# pmi_encoder_rs422_decoder.net
KiCad netlist of a schematic drawn in EAGLE
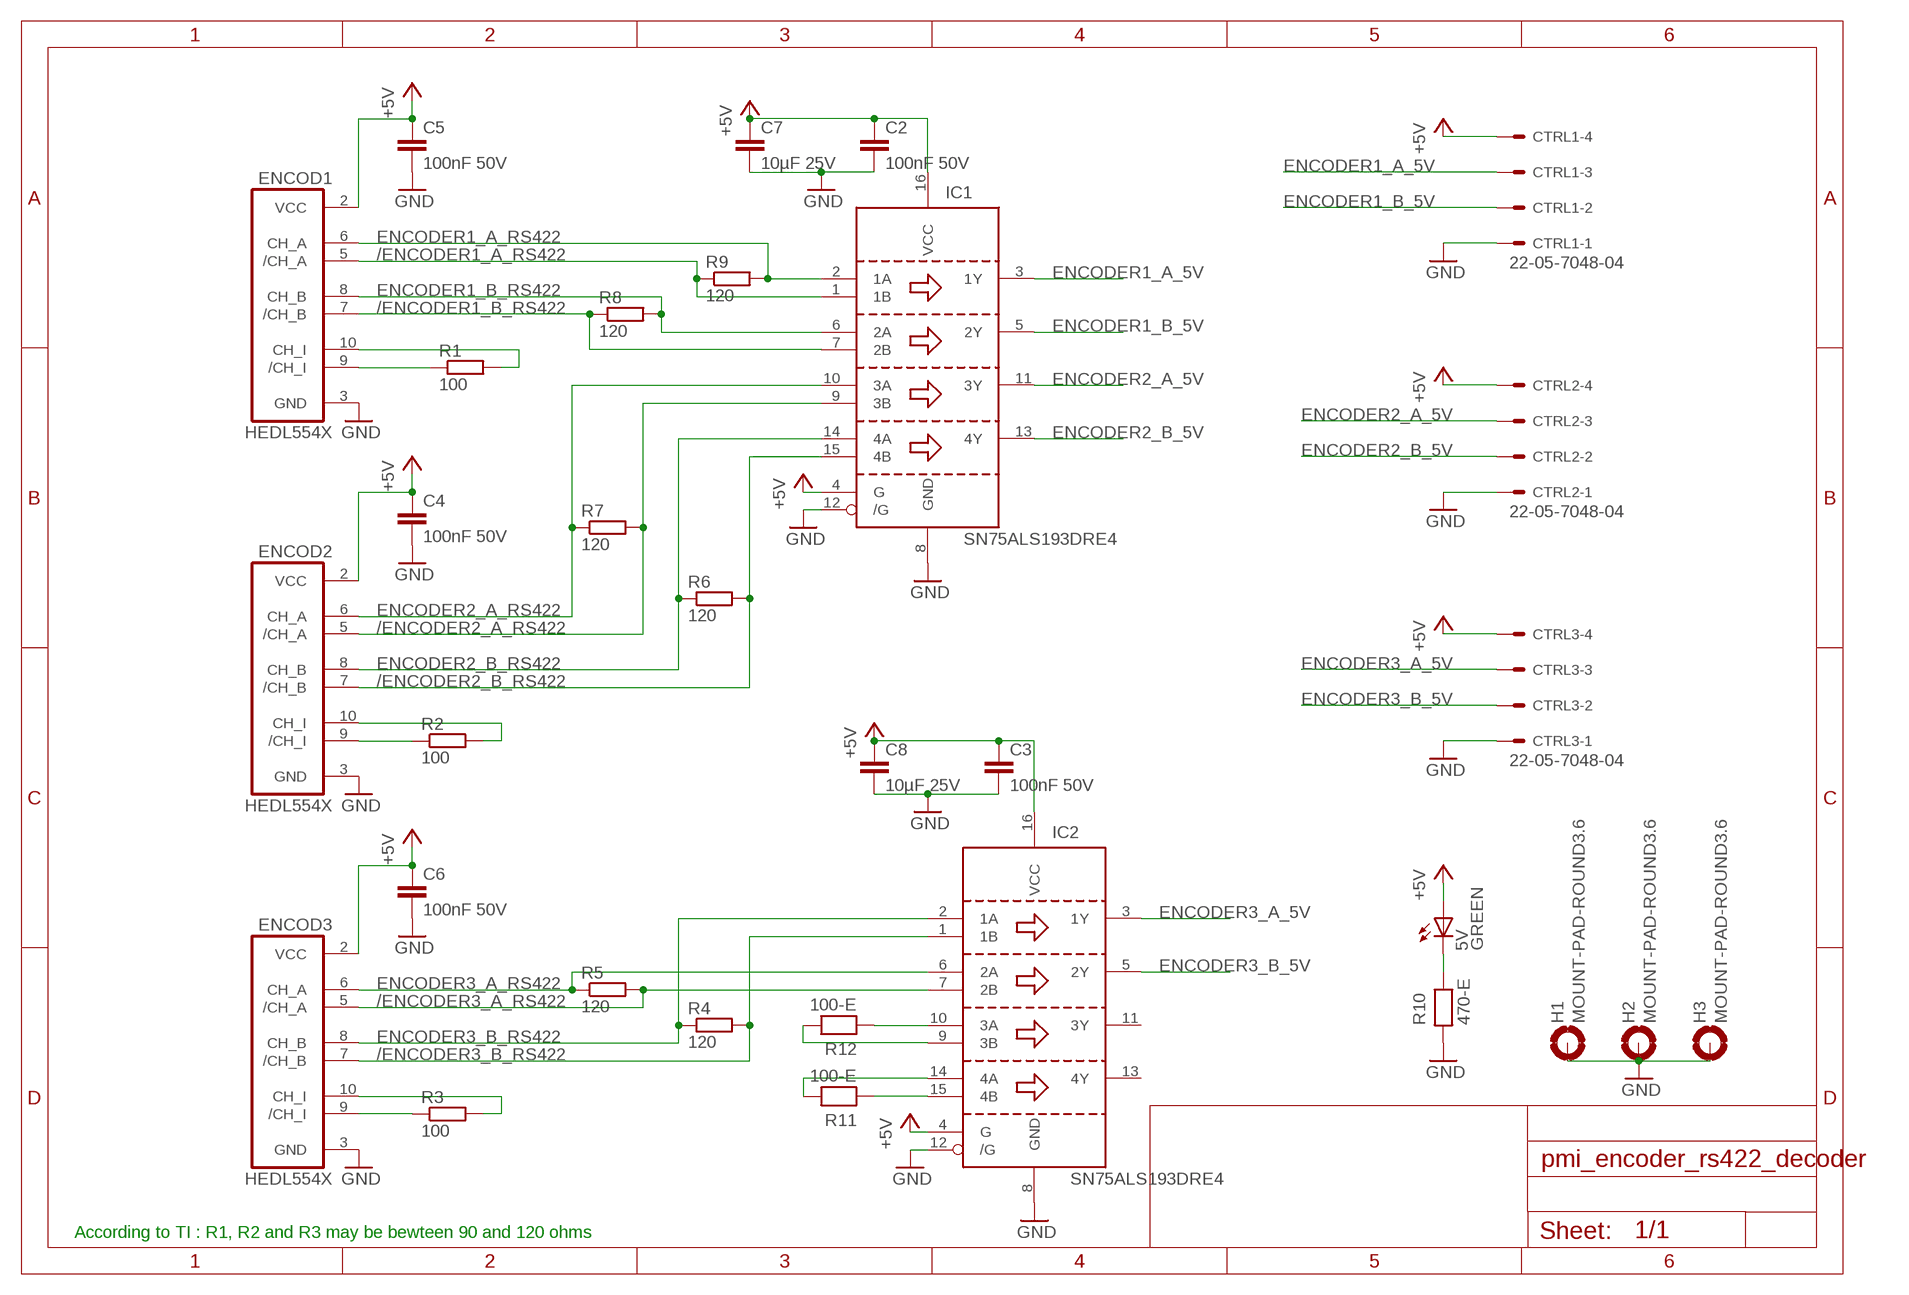
[diagram p0: schematic, sheet 1]

(export (version "E")
  (design (tool "Eeschema 10.0.6"))
  (components
    (comp (ref "5V")
      (value "GREEN")
      (footprint "eagle-import:CHIP-LED0805")
      (libsource (lib "eagle-import") (part "LED_G"))
    )
    (comp (ref "C2")
      (value "100nF 50V")
      (footprint "eagle-import:C0805")
      (libsource (lib "eagle-import") (part "100NF-E"))
    )
    (comp (ref "C3")
      (value "100nF 50V")
      (footprint "eagle-import:C0805")
      (libsource (lib "eagle-import") (part "100NF-E"))
    )
    (comp (ref "C4")
      (value "100nF 50V")
      (footprint "eagle-import:C0805")
      (libsource (lib "eagle-import") (part "100NF-E"))
    )
    (comp (ref "C5")
      (value "100nF 50V")
      (footprint "eagle-import:C0805")
      (libsource (lib "eagle-import") (part "100NF-E"))
    )
    (comp (ref "C6")
      (value "100nF 50V")
      (footprint "eagle-import:C0805")
      (libsource (lib "eagle-import") (part "100NF-E"))
    )
    (comp (ref "C7")
      (value "10µF 25V")
      (footprint "eagle-import:C1210")
      (libsource (lib "eagle-import") (part "10UF-C_25V"))
    )
    (comp (ref "C8")
      (value "10µF 25V")
      (footprint "eagle-import:C1210")
      (libsource (lib "eagle-import") (part "10UF-C_25V"))
    )
    (comp (ref "CTRL1")
      (value "22-05-7048-04")
      (footprint "eagle-import:7395-04")
      (libsource (lib "eagle-import") (part "22-?-0405-7048"))
    )
    (comp (ref "CTRL2")
      (value "22-05-7048-04")
      (footprint "eagle-import:7395-04")
      (libsource (lib "eagle-import") (part "22-?-0405-7048"))
    )
    (comp (ref "CTRL3")
      (value "22-05-7048-04")
      (footprint "eagle-import:7395-04")
      (libsource (lib "eagle-import") (part "22-?-0405-7048"))
    )
    (comp (ref "ENCOD1")
      (value "HEDL554X")
      (footprint "eagle-import:ML10")
      (libsource (lib "eagle-import") (part "HEDL554X"))
    )
    (comp (ref "ENCOD2")
      (value "HEDL554X")
      (footprint "eagle-import:ML10")
      (libsource (lib "eagle-import") (part "HEDL554X"))
    )
    (comp (ref "ENCOD3")
      (value "HEDL554X")
      (footprint "eagle-import:ML10")
      (libsource (lib "eagle-import") (part "HEDL554X"))
    )
    (comp (ref "H1")
      (value "MOUNT-PAD-ROUND3.6")
      (footprint "eagle-import:3,6-PAD")
      (libsource (lib "eagle-import") (part "MOUNT-PAD-ROUND3.6"))
    )
    (comp (ref "H2")
      (value "MOUNT-PAD-ROUND3.6")
      (footprint "eagle-import:3,6-PAD")
      (libsource (lib "eagle-import") (part "MOUNT-PAD-ROUND3.6"))
    )
    (comp (ref "H3")
      (value "MOUNT-PAD-ROUND3.6")
      (footprint "eagle-import:3,6-PAD")
      (libsource (lib "eagle-import") (part "MOUNT-PAD-ROUND3.6"))
    )
    (comp (ref "IC1")
      (value "SN75ALS193DRE4")
      (footprint "eagle-import:SO16")
      (libsource (lib "eagle-import") (part "SN75ALS193DRE4"))
    )
    (comp (ref "IC2")
      (value "SN75ALS193DRE4")
      (footprint "eagle-import:SO16")
      (libsource (lib "eagle-import") (part "SN75ALS193DRE4"))
    )
    (comp (ref "R1")
      (value "100")
      (footprint "eagle-import:0207_7")
      (libsource (lib "eagle-import") (part "R-EU_0207/7"))
    )
    (comp (ref "R2")
      (value "100")
      (footprint "eagle-import:0207_7")
      (libsource (lib "eagle-import") (part "R-EU_0207/7"))
    )
    (comp (ref "R3")
      (value "100")
      (footprint "eagle-import:0207_7")
      (libsource (lib "eagle-import") (part "R-EU_0207/7"))
    )
    (comp (ref "R4")
      (value "120")
      (footprint "eagle-import:0207_7")
      (libsource (lib "eagle-import") (part "R-EU_0207/7"))
    )
    (comp (ref "R5")
      (value "120")
      (footprint "eagle-import:0207_7")
      (libsource (lib "eagle-import") (part "R-EU_0207/7"))
    )
    (comp (ref "R6")
      (value "120")
      (footprint "eagle-import:0207_7")
      (libsource (lib "eagle-import") (part "R-EU_0207/7"))
    )
    (comp (ref "R7")
      (value "120")
      (footprint "eagle-import:0207_7")
      (libsource (lib "eagle-import") (part "R-EU_0207/7"))
    )
    (comp (ref "R8")
      (value "120")
      (footprint "eagle-import:0207_7")
      (libsource (lib "eagle-import") (part "R-EU_0207/7"))
    )
    (comp (ref "R9")
      (value "120")
      (footprint "eagle-import:0207_7")
      (libsource (lib "eagle-import") (part "R-EU_0207/7"))
    )
    (comp (ref "R10")
      (value "470-E")
      (footprint "eagle-import:R0805")
      (libsource (lib "eagle-import") (part "470-E"))
    )
    (comp (ref "R11")
      (value "100-E")
      (footprint "eagle-import:R0805")
      (libsource (lib "eagle-import") (part "100-E"))
    )
    (comp (ref "R12")
      (value "100-E")
      (footprint "eagle-import:R0805")
      (libsource (lib "eagle-import") (part "100-E"))
    )
  )
  (nets
    (net (code "1") (name "+5V") (class "Default")
      (node (ref "5V") (pin "A") (pinfunction "A_A") (pintype "passive"))
      (node (ref "C2") (pin "1") (pinfunction "1_1") (pintype "passive"))
      (node (ref "C3") (pin "1") (pinfunction "1_1") (pintype "passive"))
      (node (ref "C4") (pin "1") (pinfunction "1_1") (pintype "passive"))
      (node (ref "C5") (pin "1") (pinfunction "1_1") (pintype "passive"))
      (node (ref "C6") (pin "1") (pinfunction "1_1") (pintype "passive"))
      (node (ref "C7") (pin "1") (pinfunction "1_1") (pintype "passive"))
      (node (ref "C8") (pin "1") (pinfunction "1_1") (pintype "passive"))
      (node (ref "CTRL1") (pin "4") (pinfunction "S_4") (pintype "passive"))
      (node (ref "CTRL2") (pin "4") (pinfunction "S_4") (pintype "passive"))
      (node (ref "CTRL3") (pin "4") (pinfunction "S_4") (pintype "passive"))
      (node (ref "ENCOD1") (pin "2") (pinfunction "VCC_2") (pintype "passive"))
      (node (ref "ENCOD2") (pin "2") (pinfunction "VCC_2") (pintype "passive"))
      (node (ref "ENCOD3") (pin "2") (pinfunction "VCC_2") (pintype "passive"))
      (node (ref "IC1") (pin "16") (pinfunction "VCC_16") (pintype "power_in"))
      (node (ref "IC1") (pin "4") (pinfunction "G_4") (pintype "bidirectional"))
      (node (ref "IC2") (pin "16") (pinfunction "VCC_16") (pintype "power_in"))
      (node (ref "IC2") (pin "4") (pinfunction "G_4") (pintype "bidirectional"))
    )
    (net (code "2") (name "/ENCODER1_A_5V") (class "Default")
      (node (ref "CTRL1") (pin "3") (pinfunction "S_3") (pintype "passive"))
      (node (ref "IC1") (pin "3") (pinfunction "1Y_3") (pintype "bidirectional"))
    )
    (net (code "3") (name "/ENCODER1_A_RS422") (class "Default")
      (node (ref "ENCOD1") (pin "6") (pinfunction "CH_A_6") (pintype "passive"))
      (node (ref "IC1") (pin "2") (pinfunction "1A_2") (pintype "bidirectional"))
      (node (ref "R9") (pin "2") (pinfunction "2_2") (pintype "passive"))
    )
    (net (code "4") (name "/ENCODER1_B_5V") (class "Default")
      (node (ref "CTRL1") (pin "2") (pinfunction "S_2") (pintype "passive"))
      (node (ref "IC1") (pin "5") (pinfunction "2Y_5") (pintype "bidirectional"))
    )
    (net (code "5") (name "/ENCODER1_B_RS422") (class "Default")
      (node (ref "ENCOD1") (pin "8") (pinfunction "CH_B_8") (pintype "passive"))
      (node (ref "IC1") (pin "6") (pinfunction "2A_6") (pintype "bidirectional"))
      (node (ref "R8") (pin "2") (pinfunction "2_2") (pintype "passive"))
    )
    (net (code "6") (name "/ENCODER2_A_5V") (class "Default")
      (node (ref "CTRL2") (pin "3") (pinfunction "S_3") (pintype "passive"))
      (node (ref "IC1") (pin "11") (pinfunction "3Y_11") (pintype "bidirectional"))
    )
    (net (code "7") (name "/ENCODER2_A_RS422") (class "Default")
      (node (ref "ENCOD2") (pin "6") (pinfunction "CH_A_6") (pintype "passive"))
      (node (ref "IC1") (pin "10") (pinfunction "3A_10") (pintype "bidirectional"))
      (node (ref "R7") (pin "1") (pinfunction "1_1") (pintype "passive"))
    )
    (net (code "8") (name "/ENCODER2_B_5V") (class "Default")
      (node (ref "CTRL2") (pin "2") (pinfunction "S_2") (pintype "passive"))
      (node (ref "IC1") (pin "13") (pinfunction "4Y_13") (pintype "bidirectional"))
    )
    (net (code "9") (name "/ENCODER2_B_RS422") (class "Default")
      (node (ref "ENCOD2") (pin "8") (pinfunction "CH_B_8") (pintype "passive"))
      (node (ref "IC1") (pin "14") (pinfunction "4A_14") (pintype "bidirectional"))
      (node (ref "R6") (pin "1") (pinfunction "1_1") (pintype "passive"))
    )
    (net (code "10") (name "/ENCODER3_A_5V") (class "Default")
      (node (ref "CTRL3") (pin "3") (pinfunction "S_3") (pintype "passive"))
      (node (ref "IC2") (pin "3") (pinfunction "1Y_3") (pintype "bidirectional"))
    )
    (net (code "11") (name "/ENCODER3_A_RS422") (class "Default")
      (node (ref "ENCOD3") (pin "6") (pinfunction "CH_A_6") (pintype "passive"))
      (node (ref "IC2") (pin "6") (pinfunction "2A_6") (pintype "bidirectional"))
      (node (ref "R5") (pin "1") (pinfunction "1_1") (pintype "passive"))
    )
    (net (code "12") (name "/ENCODER3_B_5V") (class "Default")
      (node (ref "CTRL3") (pin "2") (pinfunction "S_2") (pintype "passive"))
      (node (ref "IC2") (pin "5") (pinfunction "2Y_5") (pintype "bidirectional"))
    )
    (net (code "13") (name "/ENCODER3_B_RS422") (class "Default")
      (node (ref "ENCOD3") (pin "8") (pinfunction "CH_B_8") (pintype "passive"))
      (node (ref "IC2") (pin "2") (pinfunction "1A_2") (pintype "bidirectional"))
      (node (ref "R4") (pin "1") (pinfunction "1_1") (pintype "passive"))
    )
    (net (code "14") (name "/{slash}ENCODER1_A_RS422") (class "Default")
      (node (ref "ENCOD1") (pin "5") (pinfunction "/CH_A_5") (pintype "passive"))
      (node (ref "IC1") (pin "1") (pinfunction "1B_1") (pintype "bidirectional"))
      (node (ref "R9") (pin "1") (pinfunction "1_1") (pintype "passive"))
    )
    (net (code "15") (name "/{slash}ENCODER1_B_RS422") (class "Default")
      (node (ref "ENCOD1") (pin "7") (pinfunction "/CH_B_7") (pintype "passive"))
      (node (ref "IC1") (pin "7") (pinfunction "2B_7") (pintype "bidirectional"))
      (node (ref "R8") (pin "1") (pinfunction "1_1") (pintype "passive"))
    )
    (net (code "16") (name "/{slash}ENCODER2_A_RS422") (class "Default")
      (node (ref "ENCOD2") (pin "5") (pinfunction "/CH_A_5") (pintype "passive"))
      (node (ref "IC1") (pin "9") (pinfunction "3B_9") (pintype "bidirectional"))
      (node (ref "R7") (pin "2") (pinfunction "2_2") (pintype "passive"))
    )
    (net (code "17") (name "/{slash}ENCODER2_B_RS422") (class "Default")
      (node (ref "ENCOD2") (pin "7") (pinfunction "/CH_B_7") (pintype "passive"))
      (node (ref "IC1") (pin "15") (pinfunction "4B_15") (pintype "bidirectional"))
      (node (ref "R6") (pin "2") (pinfunction "2_2") (pintype "passive"))
    )
    (net (code "18") (name "/{slash}ENCODER3_A_RS422") (class "Default")
      (node (ref "ENCOD3") (pin "5") (pinfunction "/CH_A_5") (pintype "passive"))
      (node (ref "IC2") (pin "7") (pinfunction "2B_7") (pintype "bidirectional"))
      (node (ref "R5") (pin "2") (pinfunction "2_2") (pintype "passive"))
    )
    (net (code "19") (name "/{slash}ENCODER3_B_RS422") (class "Default")
      (node (ref "ENCOD3") (pin "7") (pinfunction "/CH_B_7") (pintype "passive"))
      (node (ref "IC2") (pin "1") (pinfunction "1B_1") (pintype "bidirectional"))
      (node (ref "R4") (pin "2") (pinfunction "2_2") (pintype "passive"))
    )
    (net (code "20") (name "GND") (class "Default")
      (node (ref "C2") (pin "2") (pinfunction "2_2") (pintype "passive"))
      (node (ref "C3") (pin "2") (pinfunction "2_2") (pintype "passive"))
      (node (ref "C4") (pin "2") (pinfunction "2_2") (pintype "passive"))
      (node (ref "C5") (pin "2") (pinfunction "2_2") (pintype "passive"))
      (node (ref "C6") (pin "2") (pinfunction "2_2") (pintype "passive"))
      (node (ref "C7") (pin "2") (pinfunction "2_2") (pintype "passive"))
      (node (ref "C8") (pin "2") (pinfunction "2_2") (pintype "passive"))
      (node (ref "CTRL1") (pin "1") (pinfunction "S_1") (pintype "passive"))
      (node (ref "CTRL2") (pin "1") (pinfunction "S_1") (pintype "passive"))
      (node (ref "CTRL3") (pin "1") (pinfunction "S_1") (pintype "passive"))
      (node (ref "ENCOD1") (pin "3") (pinfunction "GND_3") (pintype "passive"))
      (node (ref "ENCOD2") (pin "3") (pinfunction "GND_3") (pintype "passive"))
      (node (ref "ENCOD3") (pin "3") (pinfunction "GND_3") (pintype "passive"))
      (node (ref "H1") (pin "B3,6") (pinfunction "MOUNT_B3,6") (pintype "passive"))
      (node (ref "H2") (pin "B3,6") (pinfunction "MOUNT_B3,6") (pintype "passive"))
      (node (ref "H3") (pin "B3,6") (pinfunction "MOUNT_B3,6") (pintype "passive"))
      (node (ref "IC1") (pin "12") (pinfunction "/G_12") (pintype "bidirectional"))
      (node (ref "IC1") (pin "8") (pinfunction "GND_8") (pintype "power_in"))
      (node (ref "IC2") (pin "12") (pinfunction "/G_12") (pintype "bidirectional"))
      (node (ref "IC2") (pin "8") (pinfunction "GND_8") (pintype "power_in"))
      (node (ref "R10") (pin "1") (pinfunction "1_1") (pintype "bidirectional"))
    )
    (net (code "21") (name "Net-(5V-PadC)") (class "Default")
      (node (ref "5V") (pin "C") (pinfunction "C_C") (pintype "passive"))
      (node (ref "R10") (pin "2") (pinfunction "2_2") (pintype "bidirectional"))
    )
    (net (code "22") (name "Net-(ENCOD1-CH_I)") (class "Default")
      (node (ref "ENCOD1") (pin "10") (pinfunction "CH_I_10") (pintype "passive"))
      (node (ref "R1") (pin "2") (pinfunction "2_2") (pintype "passive"))
    )
    (net (code "23") (name "Net-(ENCOD1-{slash}CH_I)") (class "Default")
      (node (ref "ENCOD1") (pin "9") (pinfunction "/CH_I_9") (pintype "passive"))
      (node (ref "R1") (pin "1") (pinfunction "1_1") (pintype "passive"))
    )
    (net (code "24") (name "Net-(ENCOD2-CH_I)") (class "Default")
      (node (ref "ENCOD2") (pin "10") (pinfunction "CH_I_10") (pintype "passive"))
      (node (ref "R2") (pin "2") (pinfunction "2_2") (pintype "passive"))
    )
    (net (code "25") (name "Net-(ENCOD2-{slash}CH_I)") (class "Default")
      (node (ref "ENCOD2") (pin "9") (pinfunction "/CH_I_9") (pintype "passive"))
      (node (ref "R2") (pin "1") (pinfunction "1_1") (pintype "passive"))
    )
    (net (code "26") (name "Net-(ENCOD3-CH_I)") (class "Default")
      (node (ref "ENCOD3") (pin "10") (pinfunction "CH_I_10") (pintype "passive"))
      (node (ref "R3") (pin "2") (pinfunction "2_2") (pintype "passive"))
    )
    (net (code "27") (name "Net-(ENCOD3-{slash}CH_I)") (class "Default")
      (node (ref "ENCOD3") (pin "9") (pinfunction "/CH_I_9") (pintype "passive"))
      (node (ref "R3") (pin "1") (pinfunction "1_1") (pintype "passive"))
    )
    (net (code "28") (name "Net-(IC2-3A)") (class "Default")
      (node (ref "IC2") (pin "10") (pinfunction "3A_10") (pintype "bidirectional"))
      (node (ref "R12") (pin "1") (pinfunction "1_1") (pintype "bidirectional"))
    )
    (net (code "29") (name "Net-(IC2-3B)") (class "Default")
      (node (ref "IC2") (pin "9") (pinfunction "3B_9") (pintype "bidirectional"))
      (node (ref "R12") (pin "2") (pinfunction "2_2") (pintype "bidirectional"))
    )
    (net (code "30") (name "Net-(IC2-4A)") (class "Default")
      (node (ref "IC2") (pin "14") (pinfunction "4A_14") (pintype "bidirectional"))
      (node (ref "R11") (pin "2") (pinfunction "2_2") (pintype "bidirectional"))
    )
    (net (code "31") (name "Net-(IC2-4B)") (class "Default")
      (node (ref "IC2") (pin "15") (pinfunction "4B_15") (pintype "bidirectional"))
      (node (ref "R11") (pin "1") (pinfunction "1_1") (pintype "bidirectional"))
    )
    (net (code "32") (name "unconnected-(IC2-3Y-Pad11)") (class "Default")
      (node (ref "IC2") (pin "11") (pinfunction "3Y_11") (pintype "bidirectional"))
    )
    (net (code "33") (name "unconnected-(IC2-4Y-Pad13)") (class "Default")
      (node (ref "IC2") (pin "13") (pinfunction "4Y_13") (pintype "bidirectional"))
    )
  )
)
